# CHARGER.net
KiCad netlist of a schematic drawn in Altium Designer
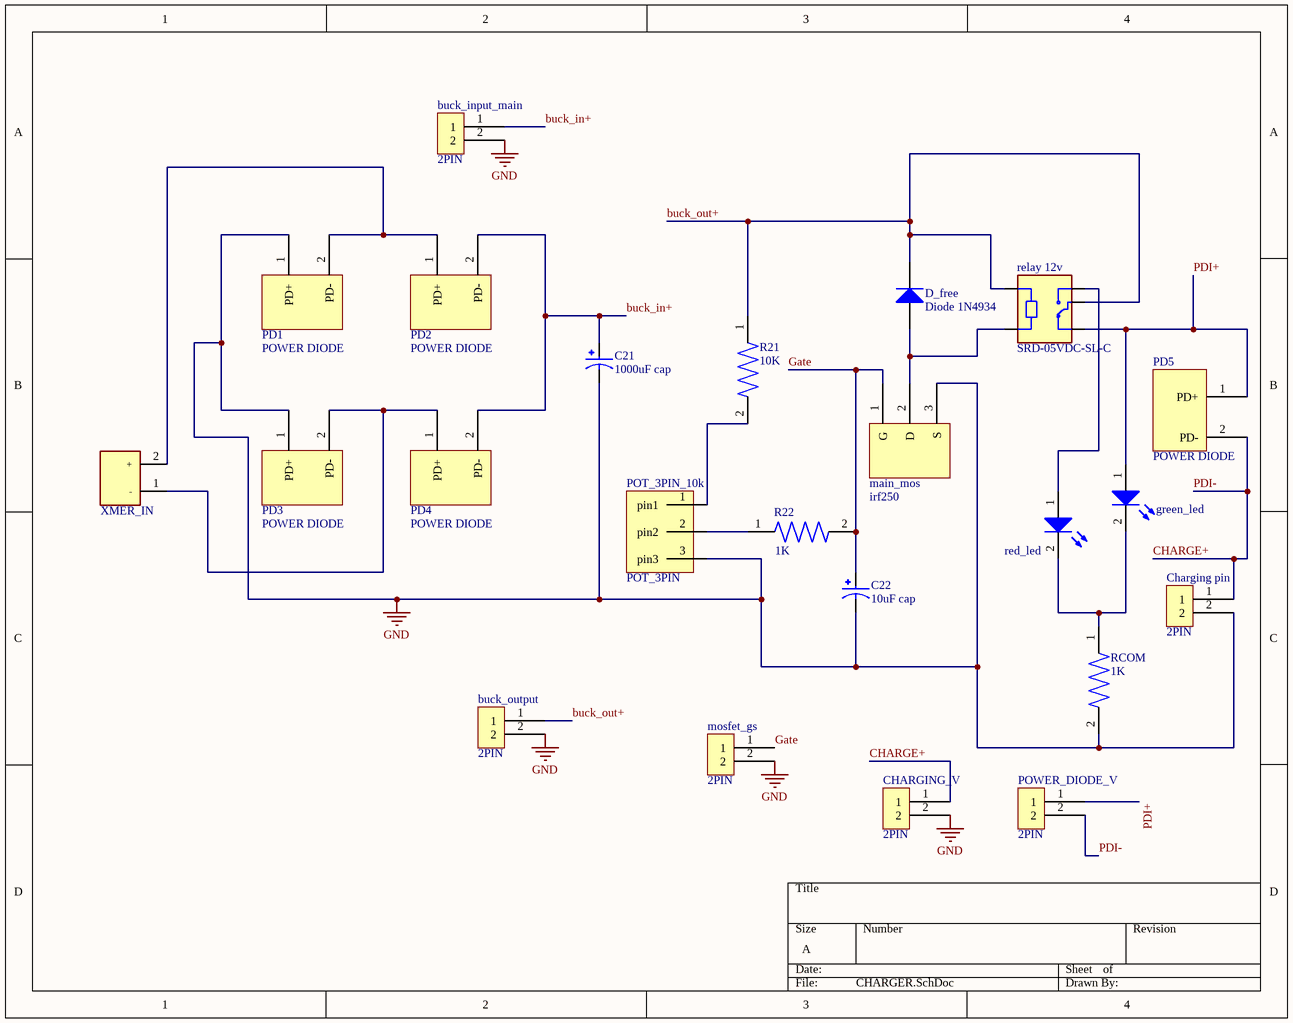
[diagram p0: CHARGER.SchDoc]

(export (version "E")
  (design (tool "Eeschema 10.0.6"))
  (components
    (comp (ref "buck_input_main")
      (value "2PIN")
      (footprint "pin2")
      (libsource (lib "Nishat_lib (4)") (part "2PIN"))
    )
    (comp (ref "buck_output")
      (value "2PIN")
      (footprint "pin2")
      (libsource (lib "Nishat_lib (4)") (part "2PIN"))
    )
    (comp (ref "C21")
      (value "1000uF cap")
      (footprint "4.7UF CAP")
      (description "CAP ALUM 4.7UF 20% 50V RADIAL")
      (fields (field (name "MP") "ECE-A1HKA4R7I") (field (name "MF") "Panasonic"))
      (libsource (lib "Nishat_lib (4)") (part "4.7uF cap"))
    )
    (comp (ref "C22")
      (value "10uF cap")
      (footprint "4.7UF CAP")
      (description "CAP ALUM 4.7UF 20% 50V RADIAL")
      (fields (field (name "MP") "ECE-A1HKA4R7I") (field (name "MF") "Panasonic"))
      (libsource (lib "Nishat_lib (4)") (part "4.7uF cap"))
    )
    (comp (ref "Charging pin")
      (value "2PIN")
      (footprint "pin2")
      (libsource (lib "Nishat_lib (4)") (part "2PIN"))
    )
    (comp (ref "CHARGING_V")
      (value "2PIN")
      (footprint "pin2")
      (libsource (lib "Nishat_lib (4)") (part "2PIN"))
    )
    (comp (ref "D_free")
      (value "Diode 1N4934")
      (footprint "DO-41")
      (description "1 Amp Fast Recovery Rectifier")
      (fields (field (name "PUBLISHER") "Altium Limited"))
      (libsource (lib "Miscellaneous Devices") (part "Diode 1N4934"))
    )
    (comp (ref "green_led")
      (value "COLOR")
      (footprint "led_2")
      (libsource (lib "Nishat_lib (4)") (part "LED_2"))
    )
    (comp (ref "main_mos")
      (value "irf250")
      (footprint "mosfetIRF250")
      (libsource (lib "MOSFETIRF250") (part "Component_1"))
    )
    (comp (ref "mosfet_gs")
      (value "2PIN")
      (footprint "pin2")
      (libsource (lib "Nishat_lib (4)") (part "2PIN"))
    )
    (comp (ref "PD1")
      (value "POWER DIODE")
      (footprint "power diode")
      (libsource (lib "POWER DIODE") (part "POWER DIODE"))
    )
    (comp (ref "PD2")
      (value "POWER DIODE")
      (footprint "power diode")
      (libsource (lib "POWER DIODE") (part "POWER DIODE"))
    )
    (comp (ref "PD3")
      (value "POWER DIODE")
      (footprint "power diode")
      (libsource (lib "POWER DIODE") (part "POWER DIODE"))
    )
    (comp (ref "PD4")
      (value "POWER DIODE")
      (footprint "power diode")
      (libsource (lib "POWER DIODE") (part "POWER DIODE"))
    )
    (comp (ref "PD5")
      (value "POWER DIODE")
      (footprint "power diode")
      (libsource (lib "") (part "POWER DIODE_1"))
    )
    (comp (ref "POT_3PIN_10k")
      (value "POT_3PIN")
      (footprint "pot_3pin")
      (libsource (lib "POT_3PIN") (part "POT_3PIN"))
    )
    (comp (ref "POWER_DIODE_V")
      (value "2PIN")
      (footprint "pin2")
      (libsource (lib "Nishat_lib (4)") (part "2PIN"))
    )
    (comp (ref "R21")
      (value "10K")
      (footprint "RESAD700W45L350D185")
      (description "1 MOhms Â±5% 0.25W, 1/4W Through Hole Resistor Axial - Carbon Film")
      (fields (field (name "MF") "TE Connectivity") (field (name "MP") "3-1623927-1"))
      (libsource (lib "3-1623927-1") (part "3-1623927-1"))
    )
    (comp (ref "R22")
      (value "1K")
      (footprint "RESAD700W45L350D185")
      (description "1 MOhms Â±5% 0.25W, 1/4W Through Hole Resistor Axial - Carbon Film")
      (fields (field (name "MF") "TE Connectivity") (field (name "MP") "3-1623927-1"))
      (libsource (lib "3-1623927-1") (part "3-1623927-1"))
    )
    (comp (ref "RCOM")
      (value "1K")
      (footprint "RESAD700W45L350D185")
      (description "1 MOhms Â±5% 0.25W, 1/4W Through Hole Resistor Axial - Carbon Film")
      (fields (field (name "MF") "TE Connectivity") (field (name "MP") "3-1623927-1"))
      (libsource (lib "3-1623927-1") (part "3-1623927-1"))
    )
    (comp (ref "red_led")
      (value "COLOR")
      (footprint "led_2")
      (libsource (lib "Nishat_lib (4)") (part "LED_2"))
    )
    (comp (ref "relay 12v")
      (value "SRD-05VDC-SL-C")
      (footprint "RELAY_SRD-05VDC-SL-C")
      (fields (field (name "MF") "Songle Relay"))
      (libsource (lib "SRD-05VDC-SL-C") (part "SRD-05VDC-SL-C"))
    )
    (comp (ref "XMER_IN")
      (value "HEADER, 2 PINS")
      (footprint "XT60 MALE")
      (description "CONNECTOR")
      (libsource (lib "Nishat_lib (4)") (part "XT60 MALE"))
    )
  )
  (nets
    (net (code "1") (name "/CHARGE+") (class "Default")
      (node (ref "CHARGING_V") (pin "1") (pinfunction "1_1") (pintype "passive"))
      (node (ref "Charging pin") (pin "1") (pinfunction "1_1") (pintype "passive"))
      (node (ref "PD5") (pin "2") (pinfunction "PD-_2") (pintype "passive"))
      (node (ref "POWER_DIODE_V") (pin "2") (pinfunction "2_2") (pintype "passive"))
    )
    (net (code "2") (name "/Gate") (class "Default")
      (node (ref "C22") (pin "P") (pinfunction "P_P") (pintype "passive"))
      (node (ref "R22") (pin "2") (pinfunction "2_2") (pintype "passive"))
      (node (ref "main_mos") (pin "1") (pinfunction "G_1") (pintype "passive"))
      (node (ref "mosfet_gs") (pin "1") (pinfunction "1_1") (pintype "passive"))
    )
    (net (code "3") (name "/PDI+") (class "Default")
      (node (ref "PD5") (pin "1") (pinfunction "PD+_1") (pintype "passive"))
      (node (ref "POWER_DIODE_V") (pin "1") (pinfunction "1_1") (pintype "passive"))
      (node (ref "green_led") (pin "1") (pinfunction "A_1") (pintype "passive"))
      (node (ref "relay 12v") (pin "NC") (pinfunction "NC_NC") (pintype "passive"))
    )
    (net (code "4") (name "/buck_in+") (class "Default")
      (node (ref "C21") (pin "P") (pinfunction "P_P") (pintype "passive"))
      (node (ref "PD2") (pin "2") (pinfunction "PD-_2") (pintype "passive"))
      (node (ref "PD4") (pin "2") (pinfunction "PD-_2") (pintype "passive"))
      (node (ref "buck_input_main") (pin "1") (pinfunction "1_1") (pintype "passive"))
    )
    (net (code "5") (name "/buck_out+") (class "Default")
      (node (ref "D_free") (pin "2") (pinfunction "K_2") (pintype "passive"))
      (node (ref "R21") (pin "1") (pinfunction "1_1") (pintype "passive"))
      (node (ref "buck_output") (pin "1") (pinfunction "1_1") (pintype "passive"))
      (node (ref "relay 12v") (pin "A1") (pinfunction "A1_A1") (pintype "passive"))
      (node (ref "relay 12v") (pin "COM") (pinfunction "COM_COM") (pintype "passive"))
    )
    (net (code "6") (name "GND") (class "Default")
      (node (ref "C21") (pin "N") (pinfunction "N_N") (pintype "passive"))
      (node (ref "C22") (pin "N") (pinfunction "N_N") (pintype "passive"))
      (node (ref "CHARGING_V") (pin "2") (pinfunction "2_2") (pintype "passive"))
      (node (ref "Charging pin") (pin "2") (pinfunction "2_2") (pintype "passive"))
      (node (ref "PD1") (pin "1") (pinfunction "PD+_1") (pintype "passive"))
      (node (ref "PD3") (pin "1") (pinfunction "PD+_1") (pintype "passive"))
      (node (ref "POT_3PIN_10k") (pin "3") (pinfunction "pin3_3") (pintype "passive"))
      (node (ref "RCOM") (pin "2") (pinfunction "2_2") (pintype "passive"))
      (node (ref "buck_input_main") (pin "2") (pinfunction "2_2") (pintype "passive"))
      (node (ref "buck_output") (pin "2") (pinfunction "2_2") (pintype "passive"))
      (node (ref "main_mos") (pin "3") (pinfunction "S_3") (pintype "passive"))
      (node (ref "mosfet_gs") (pin "2") (pinfunction "2_2") (pintype "passive"))
    )
    (net (code "7") (name "Net-(D_free-A)") (class "Default")
      (node (ref "D_free") (pin "1") (pinfunction "A_1") (pintype "passive"))
      (node (ref "main_mos") (pin "2") (pinfunction "D_2") (pintype "passive"))
      (node (ref "relay 12v") (pin "A2") (pinfunction "A2_A2") (pintype "passive"))
    )
    (net (code "8") (name "Net-(PD1-PD-)") (class "Default")
      (node (ref "PD1") (pin "2") (pinfunction "PD-_2") (pintype "passive"))
      (node (ref "PD2") (pin "1") (pinfunction "PD+_1") (pintype "passive"))
      (node (ref "XMER_IN") (pin "2") (pinfunction "+_2") (pintype "passive"))
    )
    (net (code "9") (name "Net-(PD3-PD-)") (class "Default")
      (node (ref "PD3") (pin "2") (pinfunction "PD-_2") (pintype "passive"))
      (node (ref "PD4") (pin "1") (pinfunction "PD+_1") (pintype "passive"))
      (node (ref "XMER_IN") (pin "1") (pinfunction "-_1") (pintype "passive"))
    )
    (net (code "10") (name "Net-(POT_3PIN_10k-pin1)") (class "Default")
      (node (ref "POT_3PIN_10k") (pin "1") (pinfunction "pin1_1") (pintype "passive"))
      (node (ref "R21") (pin "2") (pinfunction "2_2") (pintype "passive"))
    )
    (net (code "11") (name "Net-(POT_3PIN_10k-pin2)") (class "Default")
      (node (ref "POT_3PIN_10k") (pin "2") (pinfunction "pin2_2") (pintype "passive"))
      (node (ref "R22") (pin "1") (pinfunction "1_1") (pintype "passive"))
    )
    (net (code "12") (name "Net-(green_led-K)") (class "Default")
      (node (ref "RCOM") (pin "1") (pinfunction "1_1") (pintype "passive"))
      (node (ref "green_led") (pin "2") (pinfunction "K_2") (pintype "passive"))
      (node (ref "red_led") (pin "2") (pinfunction "K_2") (pintype "passive"))
    )
    (net (code "13") (name "Net-(red_led-A)") (class "Default")
      (node (ref "red_led") (pin "1") (pinfunction "A_1") (pintype "passive"))
      (node (ref "relay 12v") (pin "NO") (pinfunction "NO_NO") (pintype "passive"))
    )
  )
)
